# MODULIQ_Hub_ESP32-S3.net
KiCad netlist of a schematic drawn in Altium Designer
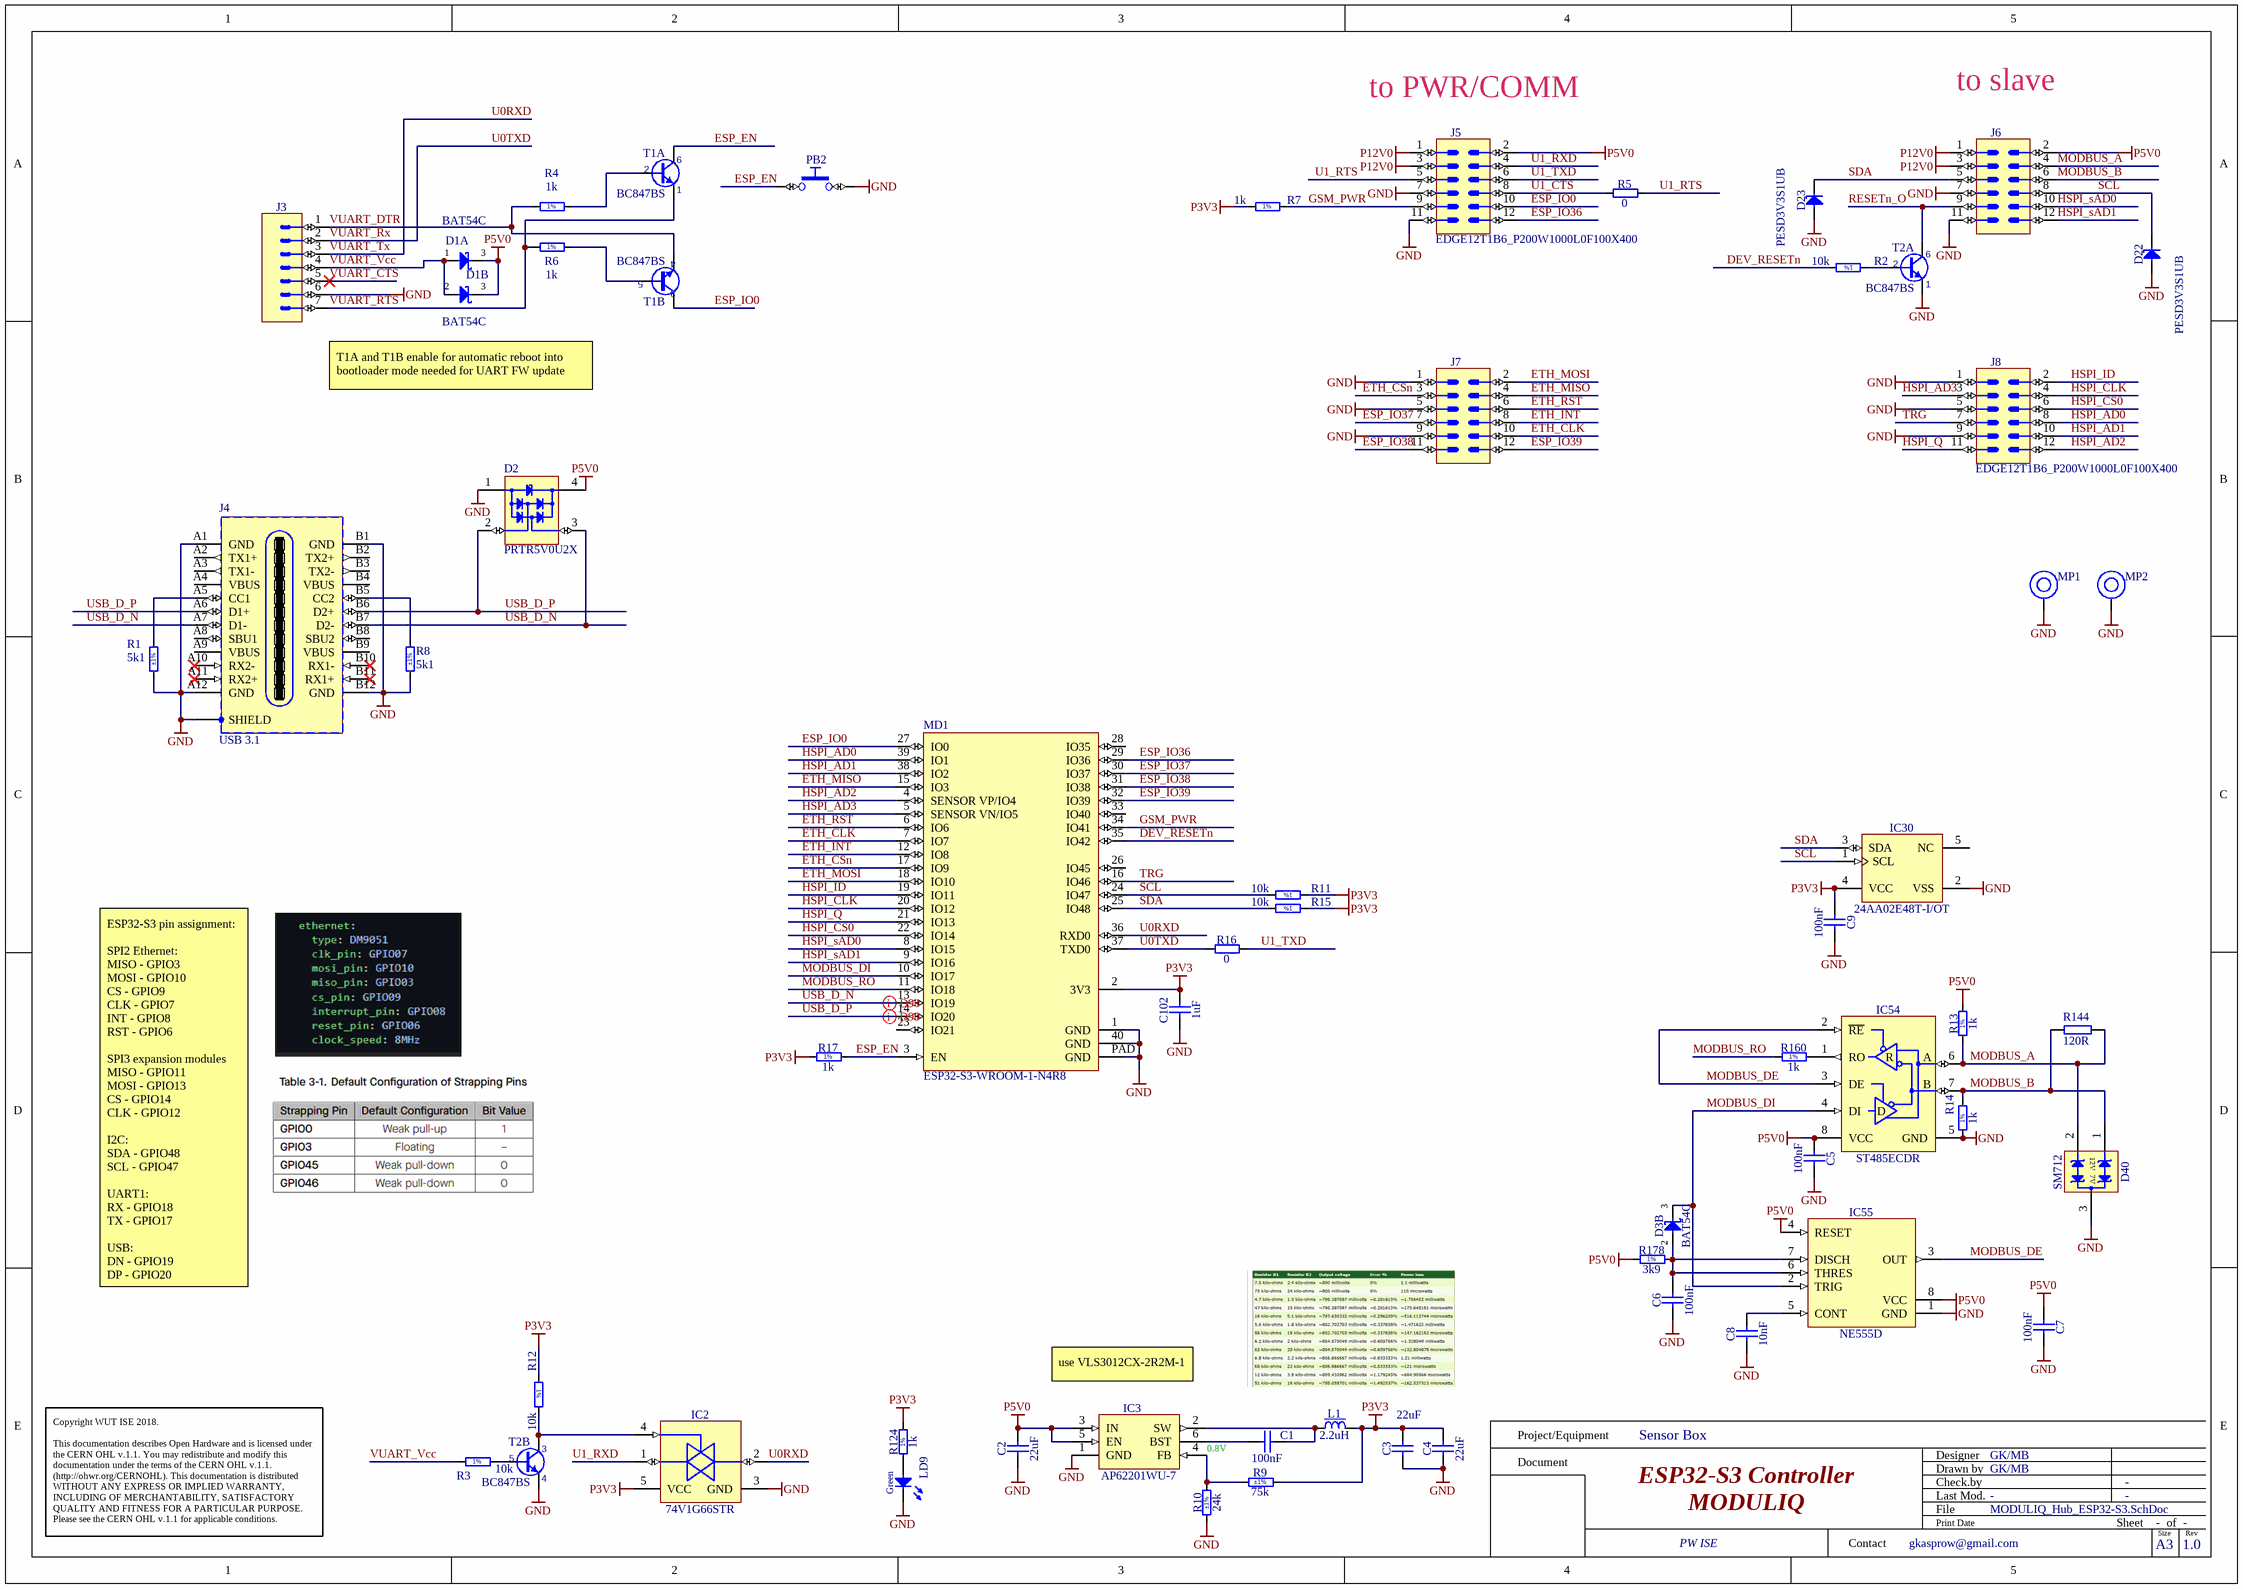
[diagram p0: MODULIQ_Hub_ESP32-S3.SchDoc]

(export (version "E")
  (design (tool "Eeschema 10.0.6"))
  (components
    (comp (ref "C1")
      (value "100nF")
      (footprint "CAPC1005X55N")
      (description "Non-polarised capacitor")
      (fields
        (field (name "PART NUMBER") "CC0402_100NF_16V_10%_X5R")
        (field (name "VOLTAGE") "16V")
        (field (name "AUTHOR") "CERN DEM JLC")
      )
      (libsource (lib "Capacitors") (part "Capacitor - non polarized"))
    )
    (comp (ref "C2")
      (value "22uF")
      (footprint "CAPC2012X145N")
      (description "Non-polarised capacitor")
      (fields
        (field (name "PART NUMBER") "CC0805_22UF_25V_20%_X5R")
        (field (name "VOLTAGE") "25V")
        (field (name "AUTHOR") "CERN DEM WB")
      )
      (libsource (lib "Capacitors") (part "Capacitor - non polarized"))
    )
    (comp (ref "C3")
      (value "22uF")
      (footprint "CAPC2012X145N")
      (description "Non-polarised capacitor")
      (fields
        (field (name "PART NUMBER") "CC0805_22UF_25V_20%_X5R")
        (field (name "VOLTAGE") "25V")
        (field (name "AUTHOR") "CERN DEM WB")
      )
      (libsource (lib "Capacitors") (part "Capacitor - non polarized"))
    )
    (comp (ref "C4")
      (value "22uF")
      (footprint "CAPC2012X145N")
      (description "Non-polarised capacitor")
      (fields
        (field (name "PART NUMBER") "CC0805_22UF_25V_20%_X5R")
        (field (name "VOLTAGE") "25V")
        (field (name "AUTHOR") "CERN DEM WB")
      )
      (libsource (lib "Capacitors") (part "Capacitor - non polarized"))
    )
    (comp (ref "C5")
      (value "100nF")
      (footprint "CAPC1005X55N")
      (description "Non-polarised capacitor")
      (fields
        (field (name "PART NUMBER") "CC0402_100NF_16V_10%_X7R")
        (field (name "VOLTAGE") "16V")
        (field (name "AUTHOR") "CERN DEM JLC")
      )
      (libsource (lib "Capacitors") (part "Capacitor - non polarized"))
    )
    (comp (ref "C6")
      (value "100nF")
      (footprint "CAPC1005X55N")
      (description "Non-polarised capacitor")
      (fields
        (field (name "PART NUMBER") "CC0402_100NF_16V_10%_X7R")
        (field (name "VOLTAGE") "16V")
        (field (name "AUTHOR") "CERN DEM JLC")
      )
      (libsource (lib "Capacitors") (part "Capacitor - non polarized"))
    )
    (comp (ref "C7")
      (value "100nF")
      (footprint "CAPC1005X55N")
      (description "Non-polarised capacitor")
      (fields
        (field (name "PART NUMBER") "CC0402_100NF_16V_10%_X7R")
        (field (name "VOLTAGE") "16V")
        (field (name "AUTHOR") "CERN DEM JLC")
      )
      (libsource (lib "Capacitors") (part "Capacitor - non polarized"))
    )
    (comp (ref "C8")
      (value "10nF")
      (footprint "CAPC1608X87N")
      (description "Non-polarised capacitor")
      (fields
        (field (name "PART NUMBER") "CC0603_10NF_50V_5%_C0G")
        (field (name "VOLTAGE") "50V")
        (field (name "AUTHOR") "CERN DEM JLC")
      )
      (libsource (lib "Capacitors") (part "Capacitor - non polarized"))
    )
    (comp (ref "C9")
      (value "100nF")
      (footprint "CAPC1005X55N")
      (description "Non-polarised capacitor")
      (fields
        (field (name "PART NUMBER") "CC0402_100NF_16V_10%_X7R")
        (field (name "VOLTAGE") "16V")
        (field (name "AUTHOR") "CERN DEM JLC")
      )
      (libsource (lib "Capacitors") (part "Capacitor - non polarized"))
    )
    (comp (ref "C102")
      (value "1uF")
      (footprint "CAPC1005X55N")
      (description "Non-polarised capacitor")
      (fields
        (field (name "PART NUMBER") "CC0402_1UF_16V_10%_X5R")
        (field (name "VOLTAGE") "16V")
        (field (name "AUTHOR") "CERN DEM JLC")
      )
      (libsource (lib "Capacitors") (part "Capacitor - non polarized"))
    )
    (comp (ref "D1")
      (value "BAT54C")
      (footprint "SOT95P240X130-3N")
      (description "Dual Common Cathode Schottky Diodes")
      (fields
        (field (name "VOLTAGE") "30V")
        (field (name "POWER") "200mA")
        (field (name "AUTHOR") "CERN DEM JLC")
      )
      (libsource (lib "ICs And Semiconductors") (part "Diode Schottky x2 A1C3_A2C3"))
    )
    (comp (ref "D2")
      (value "PRTR5V0U2X")
      (footprint "SOT190P230X110-4N")
      (description "Ultra Low Capacitance Double Rail-to-Rail ESD Protection Diode")
      (fields
        (field (name "VOLTAGE") "5.5V")
        (field (name "MANUFACTURER") "NXP SEMICONDUCTORS")
        (field (name "AUTHOR") "CERN DEM JLC")
      )
      (libsource (lib "ICs And Semiconductors") (part "PRTR5V0U2X"))
    )
    (comp (ref "D3")
      (value "BAT54C")
      (footprint "SOT95P240X130-3N")
      (description "Dual Common Cathode Schottky Diodes")
      (fields
        (field (name "VOLTAGE") "30V")
        (field (name "POWER") "200mA")
        (field (name "AUTHOR") "CERN DEM JLC")
      )
      (libsource (lib "ICs And Semiconductors") (part "Diode Schottky x2 A1C3_A2C3"))
    )
    (comp (ref "D22")
      (value "PESD3V3S1UB")
      (footprint "SODFL1608X65N")
      (description "ESD protection diode")
      (fields
        (field (name "VOLTAGE") "3V3")
        (field (name "POWER") "330W")
        (field (name "AUTHOR") "CERN DEM JLC")
      )
      (libsource (lib "ICs And Semiconductors") (part "Diode ESD"))
    )
    (comp (ref "D23")
      (value "PESD3V3S1UB")
      (footprint "SODFL1608X65N")
      (description "ESD protection diode")
      (fields
        (field (name "VOLTAGE") "3V3")
        (field (name "POWER") "330W")
        (field (name "AUTHOR") "CERN DEM JLC")
      )
      (libsource (lib "ICs And Semiconductors") (part "Diode ESD"))
    )
    (comp (ref "D40")
      (value "SM712")
      (footprint "SOT95P237X112-3N")
      (description "Asymmetrical TVS Diode for Extended Common-Mode RS-485")
      (fields
        (field (name "VOLTAGE") "12V/-7V")
        (field (name "POWER") "400W")
        (field (name "AUTHOR") "CERN DEM JLC")
      )
      (libsource (lib "ICs And Semiconductors") (part "SM712"))
    )
    (comp (ref "IC2")
      (value "74V1G66STR")
      (footprint "SOT95P280X145-5N")
      (description "Single Bilateral Switch")
      (fields (field (name "MANUFACTURER") "ST MICROELECTRONICS") (field (name "AUTHOR") "CERN DEM JLC"))
      (libsource (lib "ICs And Semiconductors") (part "741G66"))
    )
    (comp (ref "IC3")
      (value "AP62201WU-7")
      (footprint "SOT95P285X110-6N")
      (description "LIGHT LOAD IMPROVED 1.5A SYNCH DC/DC BUCK CONVERTER")
      (fields (field (name "MANUFACTURER") "DIODES INCORPORATED") (field (name "AUTHOR") "GK"))
      (libsource (lib "Regulators_SMPS") (part "PM_AP62201WU-7"))
    )
    (comp (ref "IC30")
      (value "24AA02E48T-I/OT")
      (footprint "SOT95P280X145-5N")
      (description "1.7V-5.5V, 2K I2C Serial EEPROM With EUI-48 Node Identity")
      (fields (field (name "MANUFACTURER") "MICROCHIP TECHNOLOGY") (field (name "AUTHOR") "CERN DEM MR"))
      (libsource (lib "ICs And Semiconductors") (part "24AA02E48T-I/OT"))
    )
    (comp (ref "IC54")
      (value "ST485ECDR")
      (footprint "SOIC127P600X175-8N")
      (description "±15kV ESD-Protected, Low Power  RS-485/RS-422 Transceiver")
      (fields (field (name "MANUFACTURER") "ST MICROELECTRONICS") (field (name "AUTHOR") "CERN DEM MR"))
      (libsource (lib "ICs And Semiconductors") (part "ST485EC"))
    )
    (comp (ref "IC55")
      (value "NE555D")
      (footprint "SOIC127P600X175-8N")
      (description "Precision Timer")
      (fields (field (name "MANUFACTURER") "TEXAS INSTRUMENTS") (field (name "AUTHOR") "CERN DEM JMW"))
      (libsource (lib "ICs And Semiconductors") (part "NE555"))
    )
    (comp (ref "J3")
      (value "Header 7")
      (footprint "SAMTEC_TSW-107-07-L-S-LL")
      (description "Connector 7 Male")
      (fields
        (field (name "PART NUMBER") "SAMTEC_TSW-107-07-L-S-LL")
        (field (name "MANUFACTURER") "SAMTEC")
        (field (name "AUTHOR") "CERN DEM MR")
      )
      (libsource (lib "Connectors") (part "Connector 7 Male"))
    )
    (comp (ref "J4")
      (value "USB 3.1")
      (footprint "MOLEX_2047110001")
      (description "2x12 Pin + 1 Shield  USB Type C Receptacle")
      (fields
        (field (name "PART NUMBER") "2047110001")
        (field (name "MANUFACTURER") "MOLEX")
        (field (name "AUTHOR") "Michal Beldyga")
      )
      (libsource (lib "Connectors") (part "Connector USB C 24 Pin + 1 Shield"))
    )
    (comp (ref "J5")
      (value "~")
      (footprint "EDGE12T1B6_P200W1000L0F100X400")
      (description "PCB Edge Connector 12 (2x6)")
      (fields
        (field (name "PART NUMBER") "EDGE10T1B6_P200W1000L0F100X400")
        (field (name "AUTHOR") "CERN DEM MR")
      )
      (libsource (lib "Connectors") (part "PCB Edge Connector 12 (2x6)"))
    )
    (comp (ref "J6")
      (value "~")
      (footprint "EDGE12T5B10_P200W1000L0F100X400")
      (description "PCB Edge Connector 12 (2x6)")
      (fields (field (name "PART NUMBER") "EDGE12T5B10_P200W1000L0F100X400") (field (name "AUTHOR") "GK"))
      (libsource (lib "Connectors") (part "PCB Edge Connector 12 (2x6) R"))
    )
    (comp (ref "J7")
      (value "~")
      (footprint "EDGE12T5B10_P200W1000L0F100X400")
      (description "PCB Edge Connector 12 (2x6)")
      (fields (field (name "PART NUMBER") "EDGE12T5B10_P200W1000L0F100X400") (field (name "AUTHOR") "GK"))
      (libsource (lib "Connectors") (part "PCB Edge Connector 12 (2x6) R"))
    )
    (comp (ref "J8")
      (value "~")
      (footprint "EDGE12T1B6_P200W1000L0F100X400")
      (description "PCB Edge Connector 12 (2x6)")
      (fields
        (field (name "PART NUMBER") "EDGE10T1B6_P200W1000L0F100X400")
        (field (name "AUTHOR") "CERN DEM MR")
      )
      (libsource (lib "Connectors") (part "PCB Edge Connector 12 (2x6)"))
    )
    (comp (ref "L1")
      (value "2.2uH")
      (footprint "IND_MURATA_LQH44PN_P0")
      (description "Inductor With Core")
      (fields
        (field (name "PART NUMBER") "IND_2.2UH_20%_MURATA_LQH44PN2R2MP0L")
        (field (name "POWER") "1.8A")
        (field (name "AUTHOR") "CERN DEM JLC")
      )
      (libsource (lib "Inductors & Transformers") (part "Inductor With Magnetic core"))
    )
    (comp (ref "LD9")
      (value "Green")
      (footprint "LED_KINGBRIGHT_KPH-1608CGCK")
      (description "LED Green 1C 2A")
      (fields
        (field (name "PART NUMBER") "LED_KINGBRIGHT_KPH-1608CGCK")
        (field (name "MANUFACTURER") "KINGBRIGHT")
        (field (name "AUTHOR") "CERN DEM JLC")
      )
      (libsource (lib "ICs And Semiconductors") (part "LED Green 1C 2A"))
    )
    (comp (ref "MD1")
      (value "ESP32-S3-WROOM-1-N4R8")
      (footprint "ESP32-S3-WROOM-1")
      (description "WiFi-Modul 802.11/BT 2, 4-2, 5GHz 150Mb/s")
      (fields (field (name "MANUFACTURER") "Espressif Systems"))
      (libsource (lib "mb") (part "ESP32-S3-WROOM-1-N4R8"))
    )
    (comp (ref "MP1")
      (value "M1.6 x 3mm")
      (footprint "97730306330")
      (description "WA-SMSI SMT Steel Spacer with internal Thread Bottom closed, OD 3.3mm, M1.6 x 3mm")
      (fields
        (field (name "MANUFACTURER PART NUMBER") "97730306330R")
        (field (name "MANUFACTURER") "Wurth Elektronik")
      )
      (libsource (lib "Altium_WA-SMSI (rev22a)") (part "97730306330R"))
    )
    (comp (ref "MP2")
      (value "M1.6 x 3mm")
      (footprint "97730306330")
      (description "WA-SMSI SMT Steel Spacer with internal Thread Bottom closed, OD 3.3mm, M1.6 x 3mm")
      (fields
        (field (name "MANUFACTURER PART NUMBER") "97730306330R")
        (field (name "MANUFACTURER") "Wurth Elektronik")
      )
      (libsource (lib "Altium_WA-SMSI (rev22a)") (part "97730306330R"))
    )
    (comp (ref "PB2")
      (value "Push Button")
      (footprint "PB_TYCO_FSMSM")
      (description "Push-Button Switch SPDT")
      (fields
        (field (name "PART NUMBER") "PB_TYCO_FSMSM")
        (field (name "MANUFACTURER") "TYCO ELECTRONICS")
        (field (name "AUTHOR") "CERN DEM JLC")
      )
      (libsource (lib "Eletro-mechanical") (part "PB SPST 1NO-2NO"))
    )
    (comp (ref "R1")
      (value "5k1")
      (footprint "RESC1005X40N")
      (description "Resistor - 1%")
      (fields
        (field (name "TOLERANCE") "±1%")
        (field (name "PART NUMBER") "R0402_5K1_1%_0.0625W_100PPM")
        (field (name "POWER") "0.0625W")
        (field (name "AUTHOR") "CERN DEM JLC")
      )
      (libsource (lib "Resistors") (part "Resistor - 1%"))
    )
    (comp (ref "R2")
      (value "10k")
      (footprint "RESC1005X40N")
      (description "Resistor - 1%")
      (fields
        (field (name "PART NUMBER") "R0402_10K_1%_0.0625W_100PPM")
        (field (name "POWER") "0.0625W")
        (field (name "AUTHOR") "CERN DEM JLC")
      )
      (libsource (lib "Resistors") (part "Resistor - 1%"))
    )
    (comp (ref "R3")
      (value "10k")
      (footprint "RESC1005X40N")
      (description "Resistor - 1%")
      (fields
        (field (name "PART NUMBER") "R0402_10K_1%_0.0625W_100PPM")
        (field (name "POWER") "0.0625W")
        (field (name "AUTHOR") "CERN DEM JLC")
      )
      (libsource (lib "Resistors") (part "Resistor - 1%"))
    )
    (comp (ref "R4")
      (value "1k")
      (footprint "RESC1005X40N")
      (description "Resistor - 1%")
      (fields
        (field (name "PART NUMBER") "R0402_1K_1%_0.0625W_100PPM")
        (field (name "POWER") "0.0625W")
        (field (name "AUTHOR") "CERN DEM JLC")
      )
      (libsource (lib "Resistors") (part "Resistor - 1%"))
    )
    (comp (ref "R5")
      (value "0")
      (footprint "RESC1608X55N")
      (description "Resistor")
      (fields
        (field (name "PART NUMBER") "R0603_0R_JUMPER")
        (field (name "MANUFACTURER") "GENERIC")
        (field (name "AUTHOR") "CERN DEM JLC")
      )
      (libsource (lib "Resistors") (part "Resistor"))
    )
    (comp (ref "R6")
      (value "1k")
      (footprint "RESC1005X40N")
      (description "Resistor - 1%")
      (fields
        (field (name "PART NUMBER") "R0402_1K_1%_0.0625W_100PPM")
        (field (name "POWER") "0.0625W")
        (field (name "AUTHOR") "CERN DEM JLC")
      )
      (libsource (lib "Resistors") (part "Resistor - 1%"))
    )
    (comp (ref "R7")
      (value "1k")
      (footprint "RESC1005X40N")
      (description "Resistor - 1%")
      (fields
        (field (name "PART NUMBER") "R0402_1K_1%_0.0625W_100PPM")
        (field (name "POWER") "0.0625W")
        (field (name "AUTHOR") "CERN DEM JLC")
      )
      (libsource (lib "Resistors") (part "Resistor - 1%"))
    )
    (comp (ref "R8")
      (value "5k1")
      (footprint "RESC1005X40N")
      (description "Resistor - 1%")
      (fields
        (field (name "TOLERANCE") "±1%")
        (field (name "PART NUMBER") "R0402_5K1_1%_0.0625W_100PPM")
        (field (name "POWER") "0.0625W")
        (field (name "AUTHOR") "CERN DEM JLC")
      )
      (libsource (lib "Resistors") (part "Resistor - 1%"))
    )
    (comp (ref "R9")
      (value "75k")
      (footprint "RESC1005X40N")
      (description "Resistor - 1%")
      (fields
        (field (name "TOLERANCE") "±1%")
        (field (name "PART NUMBER") "R0402_75K_1%_0.0625W_100PPM")
        (field (name "POWER") "0.0625W")
        (field (name "AUTHOR") "CERN DEM JLC")
      )
      (libsource (lib "Resistors") (part "Resistor - 1%"))
    )
    (comp (ref "R10")
      (value "24k")
      (footprint "RESC1005X40N")
      (description "Resistor - 1%")
      (fields
        (field (name "TOLERANCE") "±1%")
        (field (name "PART NUMBER") "R0402_24K_1%_0.0625W_100PPM")
        (field (name "POWER") "0.0625W")
        (field (name "AUTHOR") "CERN DEM JLC")
      )
      (libsource (lib "Resistors") (part "Resistor - 1%"))
    )
    (comp (ref "R11")
      (value "10k")
      (footprint "RESC1005X40N")
      (description "Resistor - 1%")
      (fields
        (field (name "PART NUMBER") "R0402_10K_1%_0.0625W_100PPM")
        (field (name "POWER") "0.0625W")
        (field (name "AUTHOR") "CERN DEM JLC")
      )
      (libsource (lib "Resistors") (part "Resistor - 1%"))
    )
    (comp (ref "R12")
      (value "10k")
      (footprint "RESC1005X40N")
      (description "Resistor - 1%")
      (fields
        (field (name "PART NUMBER") "R0402_10K_1%_0.0625W_100PPM")
        (field (name "POWER") "0.0625W")
        (field (name "AUTHOR") "CERN DEM JLC")
      )
      (libsource (lib "Resistors") (part "Resistor - 1%"))
    )
    (comp (ref "R13")
      (value "1k")
      (footprint "RESC1005X40N")
      (description "Resistor - 1%")
      (fields
        (field (name "PART NUMBER") "R0402_1K_1%_0.0625W_100PPM")
        (field (name "POWER") "0.0625W")
        (field (name "AUTHOR") "CERN DEM JLC")
      )
      (libsource (lib "Resistors") (part "Resistor - 1%"))
    )
    (comp (ref "R14")
      (value "1k")
      (footprint "RESC1005X40N")
      (description "Resistor - 1%")
      (fields
        (field (name "PART NUMBER") "R0402_1K_1%_0.0625W_100PPM")
        (field (name "POWER") "0.0625W")
        (field (name "AUTHOR") "CERN DEM JLC")
      )
      (libsource (lib "Resistors") (part "Resistor - 1%"))
    )
    (comp (ref "R15")
      (value "10k")
      (footprint "RESC1005X40N")
      (description "Resistor - 1%")
      (fields
        (field (name "PART NUMBER") "R0402_10K_1%_0.0625W_100PPM")
        (field (name "POWER") "0.0625W")
        (field (name "AUTHOR") "CERN DEM JLC")
      )
      (libsource (lib "Resistors") (part "Resistor - 1%"))
    )
    (comp (ref "R16")
      (value "0")
      (footprint "RESC1608X55N")
      (description "Resistor")
      (fields
        (field (name "PART NUMBER") "R0603_0R_JUMPER")
        (field (name "MANUFACTURER") "GENERIC")
        (field (name "AUTHOR") "CERN DEM JLC")
      )
      (libsource (lib "Resistors") (part "Resistor"))
    )
    (comp (ref "R17")
      (value "1k")
      (footprint "RESC1005X40N")
      (description "Resistor - 1%")
      (fields
        (field (name "PART NUMBER") "R0402_1K_1%_0.0625W_100PPM")
        (field (name "POWER") "0.0625W")
        (field (name "AUTHOR") "CERN DEM JLC")
      )
      (libsource (lib "Resistors") (part "Resistor - 1%"))
    )
    (comp (ref "R124")
      (value "1k")
      (footprint "RESC1005X40N")
      (description "Resistor - 1%")
      (fields
        (field (name "PART NUMBER") "R0402_1K_1%_0.0625W_100PPM")
        (field (name "POWER") "0.0625W")
        (field (name "AUTHOR") "CERN DEM JLC")
      )
      (libsource (lib "Resistors") (part "Resistor - 1%"))
    )
    (comp (ref "R144")
      (value "120R")
      (footprint "1206R")
      (description "SMD Resistor")
      (libsource (lib "LIBRARY_SCH") (part "RES_1206"))
    )
    (comp (ref "R160")
      (value "1k")
      (footprint "RESC1005X40N")
      (description "Resistor - 1%")
      (fields
        (field (name "PART NUMBER") "R0402_1K_1%_0.0625W_100PPM")
        (field (name "POWER") "0.0625W")
        (field (name "AUTHOR") "CERN DEM JLC")
      )
      (libsource (lib "Resistors") (part "Resistor - 1%"))
    )
    (comp (ref "R178")
      (value "3k9")
      (footprint "RESC1005X40N")
      (description "Resistor - 1%")
      (fields
        (field (name "PART NUMBER") "R0402_3K9_1%_0.0625W_100PPM")
        (field (name "POWER") "0.0625W")
        (field (name "AUTHOR") "CERN DEM JLC")
      )
      (libsource (lib "Resistors") (part "Resistor - 1%"))
    )
    (comp (ref "T1")
      (value "BC847BS")
      (footprint "SOT65P210X110-6N")
      (description "45V 100mA Dual NPN General-Purpose Transistor")
      (fields (field (name "MANUFACTURER") "NXP SEMICONDUCTORS") (field (name "AUTHOR") "CERN DEM JMW"))
      (libsource (lib "ICs And Semiconductors") (part "BC847BS"))
    )
    (comp (ref "T2")
      (value "BC847BS")
      (footprint "SOT65P210X110-6N")
      (description "45V 100mA Dual NPN General-Purpose Transistor")
      (fields (field (name "MANUFACTURER") "NXP SEMICONDUCTORS") (field (name "AUTHOR") "CERN DEM JMW"))
      (libsource (lib "ICs And Semiconductors") (part "BC847BS"))
    )
  )
  (nets
    (net (code "1") (name "/DEV_RESETn") (class "Default")
      (node (ref "MD1") (pin "35") (pinfunction "IO42_35") (pintype "bidirectional"))
      (node (ref "R2") (pin "1") (pinfunction "1_1") (pintype "passive"))
    )
    (net (code "2") (name "/ESP_EN") (class "Default")
      (node (ref "MD1") (pin "3") (pinfunction "EN_3") (pintype "input"))
      (node (ref "PB2") (pin "1") (pinfunction "1_1") (pintype "bidirectional"))
      (node (ref "R17") (pin "2") (pinfunction "2_2") (pintype "passive"))
      (node (ref "T1") (pin "6") (pinfunction "C_6") (pintype "passive"))
    )
    (net (code "3") (name "/ESP_IO0") (class "Default")
      (node (ref "J5") (pin "10") (pinfunction "10_10") (pintype "bidirectional"))
      (node (ref "MD1") (pin "27") (pinfunction "IO0_27") (pintype "bidirectional"))
      (node (ref "T1") (pin "3") (pinfunction "C_3") (pintype "passive"))
    )
    (net (code "4") (name "/ESP_IO36") (class "Default")
      (node (ref "J5") (pin "12") (pinfunction "12_12") (pintype "bidirectional"))
      (node (ref "MD1") (pin "29") (pinfunction "IO36_29") (pintype "bidirectional"))
    )
    (net (code "5") (name "/ESP_IO37") (class "Default")
      (node (ref "J7") (pin "7") (pinfunction "7_7") (pintype "bidirectional"))
      (node (ref "MD1") (pin "30") (pinfunction "IO37_30") (pintype "bidirectional"))
    )
    (net (code "6") (name "/ESP_IO38") (class "Default")
      (node (ref "J7") (pin "11") (pinfunction "11_11") (pintype "bidirectional"))
      (node (ref "MD1") (pin "31") (pinfunction "IO38_31") (pintype "bidirectional"))
    )
    (net (code "7") (name "/ESP_IO39") (class "Default")
      (node (ref "J7") (pin "12") (pinfunction "12_12") (pintype "bidirectional"))
      (node (ref "MD1") (pin "32") (pinfunction "IO39_32") (pintype "bidirectional"))
    )
    (net (code "8") (name "/ETH_CLK") (class "Default")
      (node (ref "J7") (pin "10") (pinfunction "10_10") (pintype "bidirectional"))
      (node (ref "MD1") (pin "7") (pinfunction "IO7_7") (pintype "bidirectional"))
    )
    (net (code "9") (name "/ETH_CSn") (class "Default")
      (node (ref "J7") (pin "3") (pinfunction "3_3") (pintype "bidirectional"))
      (node (ref "MD1") (pin "17") (pinfunction "IO9_17") (pintype "bidirectional"))
    )
    (net (code "10") (name "/ETH_INT") (class "Default")
      (node (ref "J7") (pin "8") (pinfunction "8_8") (pintype "bidirectional"))
      (node (ref "MD1") (pin "12") (pinfunction "IO8_12") (pintype "bidirectional"))
    )
    (net (code "11") (name "/ETH_MISO") (class "Default")
      (node (ref "J7") (pin "4") (pinfunction "4_4") (pintype "bidirectional"))
      (node (ref "MD1") (pin "15") (pinfunction "IO3_15") (pintype "bidirectional"))
    )
    (net (code "12") (name "/ETH_MOSI") (class "Default")
      (node (ref "J7") (pin "2") (pinfunction "2_2") (pintype "bidirectional"))
      (node (ref "MD1") (pin "18") (pinfunction "IO10_18") (pintype "bidirectional"))
    )
    (net (code "13") (name "/ETH_RST") (class "Default")
      (node (ref "J7") (pin "6") (pinfunction "6_6") (pintype "bidirectional"))
      (node (ref "MD1") (pin "6") (pinfunction "IO6_6") (pintype "bidirectional"))
    )
    (net (code "14") (name "/GSM_PWR") (class "Default")
      (node (ref "J5") (pin "9") (pinfunction "9_9") (pintype "bidirectional"))
      (node (ref "MD1") (pin "34") (pinfunction "IO41_34") (pintype "bidirectional"))
      (node (ref "R7") (pin "2") (pinfunction "2_2") (pintype "passive"))
    )
    (net (code "15") (name "/HSPI_AD0") (class "Default")
      (node (ref "J8") (pin "8") (pinfunction "8_8") (pintype "bidirectional"))
      (node (ref "MD1") (pin "39") (pinfunction "IO1_39") (pintype "bidirectional"))
    )
    (net (code "16") (name "/HSPI_AD1") (class "Default")
      (node (ref "J8") (pin "10") (pinfunction "10_10") (pintype "bidirectional"))
      (node (ref "MD1") (pin "38") (pinfunction "IO2_38") (pintype "bidirectional"))
    )
    (net (code "17") (name "/HSPI_AD2") (class "Default")
      (node (ref "J8") (pin "12") (pinfunction "12_12") (pintype "bidirectional"))
      (node (ref "MD1") (pin "4") (pinfunction "SENSOR_VP/IO4_4") (pintype "bidirectional"))
    )
    (net (code "18") (name "/HSPI_AD3") (class "Default")
      (node (ref "J8") (pin "3") (pinfunction "3_3") (pintype "bidirectional"))
      (node (ref "MD1") (pin "5") (pinfunction "SENSOR_VN/IO5_5") (pintype "bidirectional"))
    )
    (net (code "19") (name "/HSPI_CLK") (class "Default")
      (node (ref "J8") (pin "4") (pinfunction "4_4") (pintype "bidirectional"))
      (node (ref "MD1") (pin "20") (pinfunction "IO12_20") (pintype "bidirectional"))
    )
    (net (code "20") (name "/HSPI_CS0") (class "Default")
      (node (ref "J8") (pin "6") (pinfunction "6_6") (pintype "bidirectional"))
      (node (ref "MD1") (pin "22") (pinfunction "IO14_22") (pintype "bidirectional"))
    )
    (net (code "21") (name "/HSPI_ID") (class "Default")
      (node (ref "J8") (pin "2") (pinfunction "2_2") (pintype "bidirectional"))
      (node (ref "MD1") (pin "19") (pinfunction "IO11_19") (pintype "bidirectional"))
    )
    (net (code "22") (name "/HSPI_Q") (class "Default")
      (node (ref "J8") (pin "11") (pinfunction "11_11") (pintype "bidirectional"))
      (node (ref "MD1") (pin "21") (pinfunction "IO13_21") (pintype "bidirectional"))
    )
    (net (code "23") (name "/HSPI_sAD0") (class "Default")
      (node (ref "J6") (pin "10") (pinfunction "10_10") (pintype "bidirectional"))
      (node (ref "MD1") (pin "8") (pinfunction "IO15_8") (pintype "bidirectional"))
    )
    (net (code "24") (name "/HSPI_sAD1") (class "Default")
      (node (ref "J6") (pin "12") (pinfunction "12_12") (pintype "bidirectional"))
      (node (ref "MD1") (pin "9") (pinfunction "IO16_9") (pintype "bidirectional"))
    )
    (net (code "25") (name "/MODBUS_A") (class "Default")
      (node (ref "D40") (pin "2") (pinfunction "I/O2_2") (pintype "passive"))
      (node (ref "IC54") (pin "6") (pinfunction "A_6") (pintype "bidirectional"))
      (node (ref "J6") (pin "4") (pinfunction "4_4") (pintype "bidirectional"))
      (node (ref "R13") (pin "2") (pinfunction "2_2") (pintype "passive"))
      (node (ref "R144") (pin "2") (pinfunction "2_2") (pintype "passive"))
    )
    (net (code "26") (name "/MODBUS_B") (class "Default")
      (node (ref "D40") (pin "1") (pinfunction "I/O1_1") (pintype "passive"))
      (node (ref "IC54") (pin "7") (pinfunction "B_7") (pintype "bidirectional"))
      (node (ref "J6") (pin "6") (pinfunction "6_6") (pintype "bidirectional"))
      (node (ref "R14") (pin "1") (pinfunction "1_1") (pintype "passive"))
      (node (ref "R144") (pin "1") (pinfunction "1_1") (pintype "passive"))
    )
    (net (code "27") (name "/MODBUS_DE") (class "Default")
      (node (ref "IC54") (pin "2") (pinfunction "~{RE}_2") (pintype "input"))
      (node (ref "IC54") (pin "3") (pinfunction "DE_3") (pintype "input"))
      (node (ref "IC55") (pin "3") (pinfunction "OUT_3") (pintype "output"))
    )
    (net (code "28") (name "/MODBUS_DI") (class "Default")
      (node (ref "D3") (pin "3") (pinfunction "COMC_3") (pintype "passive"))
      (node (ref "IC54") (pin "4") (pinfunction "DI_4") (pintype "input"))
      (node (ref "IC55") (pin "2") (pinfunction "TRIG_2") (pintype "input"))
      (node (ref "MD1") (pin "10") (pinfunction "IO17_10") (pintype "bidirectional"))
    )
    (net (code "29") (name "/MODBUS_RO") (class "Default")
      (node (ref "MD1") (pin "11") (pinfunction "IO18_11") (pintype "bidirectional"))
      (node (ref "R160") (pin "1") (pinfunction "1_1") (pintype "passive"))
    )
    (net (code "30") (name "/RESETn_O") (class "Default")
      (node (ref "J6") (pin "9") (pinfunction "9_9") (pintype "bidirectional"))
      (node (ref "T2") (pin "6") (pinfunction "C_6") (pintype "passive"))
    )
    (net (code "31") (name "/SCL") (class "Default")
      (node (ref "D22") (pin "1") (pinfunction "C_1") (pintype "passive"))
      (node (ref "IC30") (pin "1") (pinfunction "SCL_1") (pintype "input"))
      (node (ref "J6") (pin "8") (pinfunction "8_8") (pintype "bidirectional"))
      (node (ref "MD1") (pin "24") (pinfunction "IO47_24") (pintype "bidirectional"))
      (node (ref "R11") (pin "1") (pinfunction "1_1") (pintype "passive"))
    )
    (net (code "32") (name "/SDA") (class "Default")
      (node (ref "D23") (pin "1") (pinfunction "C_1") (pintype "passive"))
      (node (ref "IC30") (pin "3") (pinfunction "SDA_3") (pintype "bidirectional"))
      (node (ref "J6") (pin "5") (pinfunction "5_5") (pintype "bidirectional"))
      (node (ref "MD1") (pin "25") (pinfunction "IO48_25") (pintype "bidirectional"))
      (node (ref "R15") (pin "1") (pinfunction "1_1") (pintype "passive"))
    )
    (net (code "33") (name "/TRG") (class "Default")
      (node (ref "J8") (pin "7") (pinfunction "7_7") (pintype "bidirectional"))
      (node (ref "MD1") (pin "16") (pinfunction "IO46_16") (pintype "bidirectional"))
    )
    (net (code "34") (name "/U0RXD") (class "Default")
      (node (ref "IC2") (pin "2") (pinfunction "~{D0}_2") (pintype "bidirectional"))
      (node (ref "J3") (pin "3") (pinfunction "3_3") (pintype "bidirectional"))
      (node (ref "MD1") (pin "36") (pinfunction "RXD0_36") (pintype "bidirectional"))
    )
    (net (code "35") (name "/U0TXD") (class "Default")
      (node (ref "J3") (pin "2") (pinfunction "2_2") (pintype "bidirectional"))
      (node (ref "MD1") (pin "37") (pinfunction "TXD0_37") (pintype "bidirectional"))
      (node (ref "R16") (pin "2") (pinfunction "2_2") (pintype "passive"))
    )
    (net (code "36") (name "/U1_CTS") (class "Default")
      (node (ref "J5") (pin "8") (pinfunction "8_8") (pintype "bidirectional"))
      (node (ref "R5") (pin "1") (pinfunction "1_1") (pintype "passive"))
    )
    (net (code "37") (name "/U1_RTS") (class "Default")
      (node (ref "J5") (pin "5") (pinfunction "5_5") (pintype "bidirectional"))
      (node (ref "R5") (pin "2") (pinfunction "2_2") (pintype "passive"))
    )
    (net (code "38") (name "/U1_RXD") (class "Default")
      (node (ref "IC2") (pin "1") (pinfunction "D0_1") (pintype "bidirectional"))
      (node (ref "J5") (pin "4") (pinfunction "4_4") (pintype "bidirectional"))
    )
    (net (code "39") (name "/U1_TXD") (class "Default")
      (node (ref "J5") (pin "6") (pinfunction "6_6") (pintype "bidirectional"))
      (node (ref "R16") (pin "1") (pinfunction "1_1") (pintype "passive"))
    )
    (net (code "40") (name "/USB_D_N") (class "Default")
      (node (ref "D2") (pin "3") (pinfunction "I/O2_3") (pintype "bidirectional"))
      (node (ref "J4") (pin "A7") (pinfunction "D1-_A7") (pintype "bidirectional"))
      (node (ref "J4") (pin "B7") (pinfunction "D2-_B7") (pintype "bidirectional"))
      (node (ref "MD1") (pin "13") (pinfunction "IO19_13") (pintype "bidirectional"))
    )
    (net (code "41") (name "/USB_D_P") (class "Default")
      (node (ref "D2") (pin "2") (pinfunction "I/O1_2") (pintype "bidirectional"))
      (node (ref "J4") (pin "A6") (pinfunction "D1+_A6") (pintype "bidirectional"))
      (node (ref "J4") (pin "B6") (pinfunction "D2+_B6") (pintype "bidirectional"))
      (node (ref "MD1") (pin "14") (pinfunction "IO20_14") (pintype "bidirectional"))
    )
    (net (code "42") (name "/VUART_CTS") (class "Default")
      (node (ref "J3") (pin "5") (pinfunction "5_5") (pintype "bidirectional+no_connect"))
    )
    (net (code "43") (name "/VUART_DTR") (class "Default")
      (node (ref "J3") (pin "1") (pinfunction "1_1") (pintype "bidirectional"))
      (node (ref "R4") (pin "1") (pinfunction "1_1") (pintype "passive"))
      (node (ref "T1") (pin "4") (pinfunction "E_4") (pintype "passive"))
    )
    (net (code "44") (name "/VUART_RTS") (class "Default")
      (node (ref "J3") (pin "7") (pinfunction "7_7") (pintype "bidirectional"))
      (node (ref "R6") (pin "1") (pinfunction "1_1") (pintype "passive"))
      (node (ref "T1") (pin "1") (pinfunction "E_1") (pintype "passive"))
    )
    (net (code "45") (name "/VUART_Vcc") (class "Default")
      (node (ref "D1") (pin "1") (pinfunction "A_1") (pintype "passive"))
      (node (ref "D1") (pin "2") (pinfunction "A_2") (pintype "passive"))
      (node (ref "J3") (pin "4") (pinfunction "4_4") (pintype "bidirectional"))
      (node (ref "R3") (pin "2") (pinfunction "2_2") (pintype "passive"))
    )
    (net (code "46") (name "GND") (class "Default")
      (node (ref "C102") (pin "1") (pinfunction "1_1") (pintype "passive"))
      (node (ref "C2") (pin "1") (pinfunction "1_1") (pintype "passive"))
      (node (ref "C3") (pin "1") (pinfunction "1_1") (pintype "passive"))
      (node (ref "C4") (pin "1") (pinfunction "1_1") (pintype "passive"))
      (node (ref "C5") (pin "2") (pinfunction "2_2") (pintype "passive"))
      (node (ref "C6") (pin "1") (pinfunction "1_1") (pintype "passive"))
      (node (ref "C7") (pin "2") (pinfunction "2_2") (pintype "passive"))
      (node (ref "C8") (pin "1") (pinfunction "1_1") (pintype "passive"))
      (node (ref "C9") (pin "2") (pinfunction "2_2") (pintype "passive"))
      (node (ref "D2") (pin "1") (pinfunction "GND_1") (pintype "power_in"))
      (node (ref "D22") (pin "2") (pinfunction "A_2") (pintype "passive"))
      (node (ref "D23") (pin "2") (pinfunction "A_2") (pintype "passive"))
      (node (ref "D40") (pin "3") (pinfunction "GND_3") (pintype "passive"))
      (node (ref "IC2") (pin "3") (pinfunction "GND_3") (pintype "power_in"))
      (node (ref "IC3") (pin "1") (pinfunction "GND_1") (pintype "power_in"))
      (node (ref "IC30") (pin "2") (pinfunction "VSS_2") (pintype "power_in"))
      (node (ref "IC54") (pin "5") (pinfunction "GND_5") (pintype "power_in"))
      (node (ref "IC55") (pin "1") (pinfunction "GND_1") (pintype "power_in"))
      (node (ref "J3") (pin "6") (pinfunction "6_6") (pintype "bidirectional"))
      (node (ref "J4") (pin "A1") (pinfunction "GND_A1") (pintype "power_in"))
      (node (ref "J4") (pin "A12") (pinfunction "GND_A12") (pintype "power_in"))
      (node (ref "J4") (pin "B1") (pinfunction "GND_B1") (pintype "power_in"))
      (node (ref "J4") (pin "B12") (pinfunction "GND_B12") (pintype "power_in"))
      (node (ref "J4") (pin "SHIELD") (pinfunction "SHIELD_SHIELD") (pintype "power_in"))
      (node (ref "J5") (pin "11") (pinfunction "11_11") (pintype "bidirectional"))
      (node (ref "J5") (pin "7") (pinfunction "7_7") (pintype "bidirectional"))
      (node (ref "J6") (pin "11") (pinfunction "11_11") (pintype "bidirectional"))
      (node (ref "J6") (pin "7") (pinfunction "7_7") (pintype "bidirectional"))
      (node (ref "J7") (pin "1") (pinfunction "1_1") (pintype "bidirectional"))
      (node (ref "J7") (pin "5") (pinfunction "5_5") (pintype "bidirectional"))
      (node (ref "J7") (pin "9") (pinfunction "9_9") (pintype "bidirectional"))
      (node (ref "J8") (pin "1") (pinfunction "1_1") (pintype "bidirectional"))
      (node (ref "J8") (pin "5") (pinfunction "5_5") (pintype "bidirectional"))
      (node (ref "J8") (pin "9") (pinfunction "9_9") (pintype "bidirectional"))
      (node (ref "LD9") (pin "1") (pinfunction "C_1") (pintype "passive"))
      (node (ref "MD1") (pin "1") (pinfunction "GND_1") (pintype "power_in"))
      (node (ref "MD1") (pin "40") (pinfunction "GND_40") (pintype "power_in"))
      (node (ref "MD1") (pin "PAD") (pinfunction "GND_PAD") (pintype "power_in"))
      (node (ref "MP1") (pin "1") (pinfunction "1_1") (pintype "passive"))
      (node (ref "MP2") (pin "1") (pinfunction "1_1") (pintype "passive"))
      (node (ref "PB2") (pin "2") (pinfunction "2_2") (pintype "bidirectional"))
      (node (ref "R1") (pin "1") (pinfunction "1_1") (pintype "passive"))
      (node (ref "R10") (pin "1") (pinfunction "1_1") (pintype "passive"))
      (node (ref "R14") (pin "2") (pinfunction "2_2") (pintype "passive"))
      (node (ref "R8") (pin "1") (pinfunction "1_1") (pintype "passive"))
      (node (ref "T2") (pin "1") (pinfunction "E_1") (pintype "passive"))
      (node (ref "T2") (pin "4") (pinfunction "E_4") (pintype "passive"))
    )
    (net (code "47") (name "Net-(D3B-A)") (class "Default")
      (node (ref "C6") (pin "2") (pinfunction "2_2") (pintype "passive"))
      (node (ref "D3") (pin "2") (pinfunction "A_2") (pintype "passive"))
      (node (ref "IC55") (pin "6") (pinfunction "THRES_6") (pintype "input"))
      (node (ref "IC55") (pin "7") (pinfunction "DISCH_7") (pintype "input"))
      (node (ref "R178") (pin "2") (pinfunction "2_2") (pintype "passive"))
    )
    (net (code "48") (name "Net-(IC2-~{D1})") (class "Default")
      (node (ref "IC2") (pin "4") (pinfunction "~{D1}_4") (pintype "input"))
      (node (ref "R12") (pin "1") (pinfunction "1_1") (pintype "passive"))
      (node (ref "T2") (pin "3") (pinfunction "C_3") (pintype "passive"))
    )
    (net (code "49") (name "Net-(IC3-BST)") (class "Default")
      (node (ref "C1") (pin "1") (pinfunction "1_1") (pintype "passive"))
      (node (ref "IC3") (pin "6") (pinfunction "BST_6") (pintype "passive"))
    )
    (net (code "50") (name "Net-(IC3-FB)") (class "Default")
      (node (ref "IC3") (pin "4") (pinfunction "FB_4") (pintype "input"))
      (node (ref "R10") (pin "2") (pinfunction "2_2") (pintype "passive"))
      (node (ref "R9") (pin "1") (pinfunction "1_1") (pintype "passive"))
    )
    (net (code "51") (name "Net-(IC3-SW)") (class "Default")
      (node (ref "C1") (pin "2") (pinfunction "2_2") (pintype "passive"))
      (node (ref "IC3") (pin "2") (pinfunction "SW_2") (pintype "output"))
      (node (ref "L1") (pin "1") (pinfunction "1_1") (pintype "passive"))
    )
    (net (code "52") (name "Net-(IC54-RO)") (class "Default")
      (node (ref "IC54") (pin "1") (pinfunction "RO_1") (pintype "output"))
      (node (ref "R160") (pin "2") (pinfunction "2_2") (pintype "passive"))
    )
    (net (code "53") (name "Net-(IC55-CONT)") (class "Default")
      (node (ref "C8") (pin "2") (pinfunction "2_2") (pintype "passive"))
      (node (ref "IC55") (pin "5") (pinfunction "CONT_5") (pintype "input"))
    )
    (net (code "54") (name "Net-(J4-CC1)") (class "Default")
      (node (ref "J4") (pin "A5") (pinfunction "CC1_A5") (pintype "bidirectional"))
      (node (ref "R1") (pin "2") (pinfunction "2_2") (pintype "passive"))
    )
    (net (code "55") (name "Net-(J4-CC2)") (class "Default")
      (node (ref "J4") (pin "B5") (pinfunction "CC2_B5") (pintype "bidirectional"))
      (node (ref "R8") (pin "2") (pinfunction "2_2") (pintype "passive"))
    )
    (net (code "56") (name "Net-(LD9-A)") (class "Default")
      (node (ref "LD9") (pin "2") (pinfunction "A_2") (pintype "passive"))
      (node (ref "R124") (pin "1") (pinfunction "1_1") (pintype "passive"))
    )
    (net (code "57") (name "Net-(T1A-B)") (class "Default")
      (node (ref "R4") (pin "2") (pinfunction "2_2") (pintype "passive"))
      (node (ref "T1") (pin "2") (pinfunction "B_2") (pintype "passive"))
    )
    (net (code "58") (name "Net-(T1B-B)") (class "Default")
      (node (ref "R6") (pin "2") (pinfunction "2_2") (pintype "passive"))
      (node (ref "T1") (pin "5") (pinfunction "B_5") (pintype "passive"))
    )
    (net (code "59") (name "Net-(T2A-B)") (class "Default")
      (node (ref "R2") (pin "2") (pinfunction "2_2") (pintype "passive"))
      (node (ref "T2") (pin "2") (pinfunction "B_2") (pintype "passive"))
    )
    (net (code "60") (name "Net-(T2B-B)") (class "Default")
      (node (ref "R3") (pin "1") (pinfunction "1_1") (pintype "passive"))
      (node (ref "T2") (pin "5") (pinfunction "B_5") (pintype "passive"))
    )
    (net (code "61") (name "P3V3") (class "Default")
      (node (ref "C102") (pin "2") (pinfunction "2_2") (pintype "passive"))
      (node (ref "C3") (pin "2") (pinfunction "2_2") (pintype "passive"))
      (node (ref "C4") (pin "2") (pinfunction "2_2") (pintype "passive"))
      (node (ref "C9") (pin "1") (pinfunction "1_1") (pintype "passive"))
      (node (ref "IC2") (pin "5") (pinfunction "VCC_5") (pintype "power_in"))
      (node (ref "IC30") (pin "4") (pinfunction "VCC_4") (pintype "power_in"))
      (node (ref "L1") (pin "2") (pinfunction "2_2") (pintype "passive"))
      (node (ref "MD1") (pin "2") (pinfunction "3V3_2") (pintype "power_in"))
      (node (ref "R11") (pin "2") (pinfunction "2_2") (pintype "passive"))
      (node (ref "R12") (pin "2") (pinfunction "2_2") (pintype "passive"))
      (node (ref "R124") (pin "2") (pinfunction "2_2") (pintype "passive"))
      (node (ref "R15") (pin "2") (pinfunction "2_2") (pintype "passive"))
      (node (ref "R17") (pin "1") (pinfunction "1_1") (pintype "passive"))
      (node (ref "R7") (pin "1") (pinfunction "1_1") (pintype "passive"))
      (node (ref "R9") (pin "2") (pinfunction "2_2") (pintype "passive"))
    )
    (net (code "62") (name "P5V0") (class "Default")
      (node (ref "C2") (pin "2") (pinfunction "2_2") (pintype "passive"))
      (node (ref "C5") (pin "1") (pinfunction "1_1") (pintype "passive"))
      (node (ref "C7") (pin "1") (pinfunction "1_1") (pintype "passive"))
      (node (ref "D1") (pin "3") (pinfunction "COMC_3") (pintype "passive"))
      (node (ref "D2") (pin "4") (pinfunction "VCC_4") (pintype "power_in"))
      (node (ref "IC3") (pin "3") (pinfunction "IN_3") (pintype "input"))
      (node (ref "IC3") (pin "5") (pinfunction "EN_5") (pintype "input"))
      (node (ref "IC54") (pin "8") (pinfunction "VCC_8") (pintype "power_in"))
      (node (ref "IC55") (pin "4") (pinfunction "RESET_4") (pintype "input"))
      (node (ref "IC55") (pin "8") (pinfunction "VCC_8") (pintype "power_in"))
      (node (ref "J5") (pin "2") (pinfunction "2_2") (pintype "bidirectional"))
      (node (ref "J6") (pin "2") (pinfunction "2_2") (pintype "bidirectional"))
      (node (ref "R13") (pin "1") (pinfunction "1_1") (pintype "passive"))
      (node (ref "R178") (pin "1") (pinfunction "1_1") (pintype "passive"))
    )
    (net (code "63") (name "P12V0") (class "Default")
      (node (ref "J5") (pin "1") (pinfunction "1_1") (pintype "bidirectional"))
      (node (ref "J5") (pin "3") (pinfunction "3_3") (pintype "bidirectional"))
      (node (ref "J6") (pin "1") (pinfunction "1_1") (pintype "bidirectional"))
      (node (ref "J6") (pin "3") (pinfunction "3_3") (pintype "bidirectional"))
    )
    (net (code "64") (name "unconnected-(IC30-NC-Pad5)") (class "Default")
      (node (ref "IC30") (pin "5") (pinfunction "NC_5") (pintype "passive"))
    )
    (net (code "65") (name "unconnected-(J4-RX1+-PadB11)") (class "Default")
      (node (ref "J4") (pin "B11") (pinfunction "RX1+_B11") (pintype "input+no_connect"))
    )
    (net (code "66") (name "unconnected-(J4-RX1--PadB10)") (class "Default")
      (node (ref "J4") (pin "B10") (pinfunction "RX1-_B10") (pintype "input+no_connect"))
    )
    (net (code "67") (name "unconnected-(J4-RX2+-PadA11)") (class "Default")
      (node (ref "J4") (pin "A11") (pinfunction "RX2+_A11") (pintype "input+no_connect"))
    )
    (net (code "68") (name "unconnected-(J4-RX2--PadA10)") (class "Default")
      (node (ref "J4") (pin "A10") (pinfunction "RX2-_A10") (pintype "input+no_connect"))
    )
    (net (code "69") (name "unconnected-(J4-SBU1-PadA8)") (class "Default")
      (node (ref "J4") (pin "A8") (pinfunction "SBU1_A8") (pintype "bidirectional"))
    )
    (net (code "70") (name "unconnected-(J4-SBU2-PadB8)") (class "Default")
      (node (ref "J4") (pin "B8") (pinfunction "SBU2_B8") (pintype "bidirectional"))
    )
    (net (code "71") (name "unconnected-(J4-TX1+-PadA2)") (class "Default")
      (node (ref "J4") (pin "A2") (pinfunction "TX1+_A2") (pintype "output"))
    )
    (net (code "72") (name "unconnected-(J4-TX1--PadA3)") (class "Default")
      (node (ref "J4") (pin "A3") (pinfunction "TX1-_A3") (pintype "output"))
    )
    (net (code "73") (name "unconnected-(J4-TX2+-PadB2)") (class "Default")
      (node (ref "J4") (pin "B2") (pinfunction "TX2+_B2") (pintype "output"))
    )
    (net (code "74") (name "unconnected-(J4-TX2--PadB3)") (class "Default")
      (node (ref "J4") (pin "B3") (pinfunction "TX2-_B3") (pintype "output"))
    )
    (net (code "75") (name "unconnected-(J4-VBUS-PadA4)") (class "Default")
      (node (ref "J4") (pin "A4") (pinfunction "VBUS_A4") (pintype "power_in"))
    )
    (net (code "76") (name "unconnected-(J4-VBUS-PadA9)") (class "Default")
      (node (ref "J4") (pin "A9") (pinfunction "VBUS_A9") (pintype "power_in"))
    )
    (net (code "77") (name "unconnected-(J4-VBUS-PadB4)") (class "Default")
      (node (ref "J4") (pin "B4") (pinfunction "VBUS_B4") (pintype "power_in"))
    )
    (net (code "78") (name "unconnected-(J4-VBUS-PadB9)") (class "Default")
      (node (ref "J4") (pin "B9") (pinfunction "VBUS_B9") (pintype "power_in"))
    )
    (net (code "79") (name "unconnected-(MD1-IO21-Pad23)") (class "Default")
      (node (ref "MD1") (pin "23") (pinfunction "IO21_23") (pintype "bidirectional"))
    )
    (net (code "80") (name "unconnected-(MD1-IO35-Pad28)") (class "Default")
      (node (ref "MD1") (pin "28") (pinfunction "IO35_28") (pintype "bidirectional"))
    )
    (net (code "81") (name "unconnected-(MD1-IO40-Pad33)") (class "Default")
      (node (ref "MD1") (pin "33") (pinfunction "IO40_33") (pintype "bidirectional"))
    )
    (net (code "82") (name "unconnected-(MD1-IO45-Pad26)") (class "Default")
      (node (ref "MD1") (pin "26") (pinfunction "IO45_26") (pintype "bidirectional"))
    )
  )
)
